# TubeAmp_driver.net
KiCad netlist of a schematic drawn in EAGLE
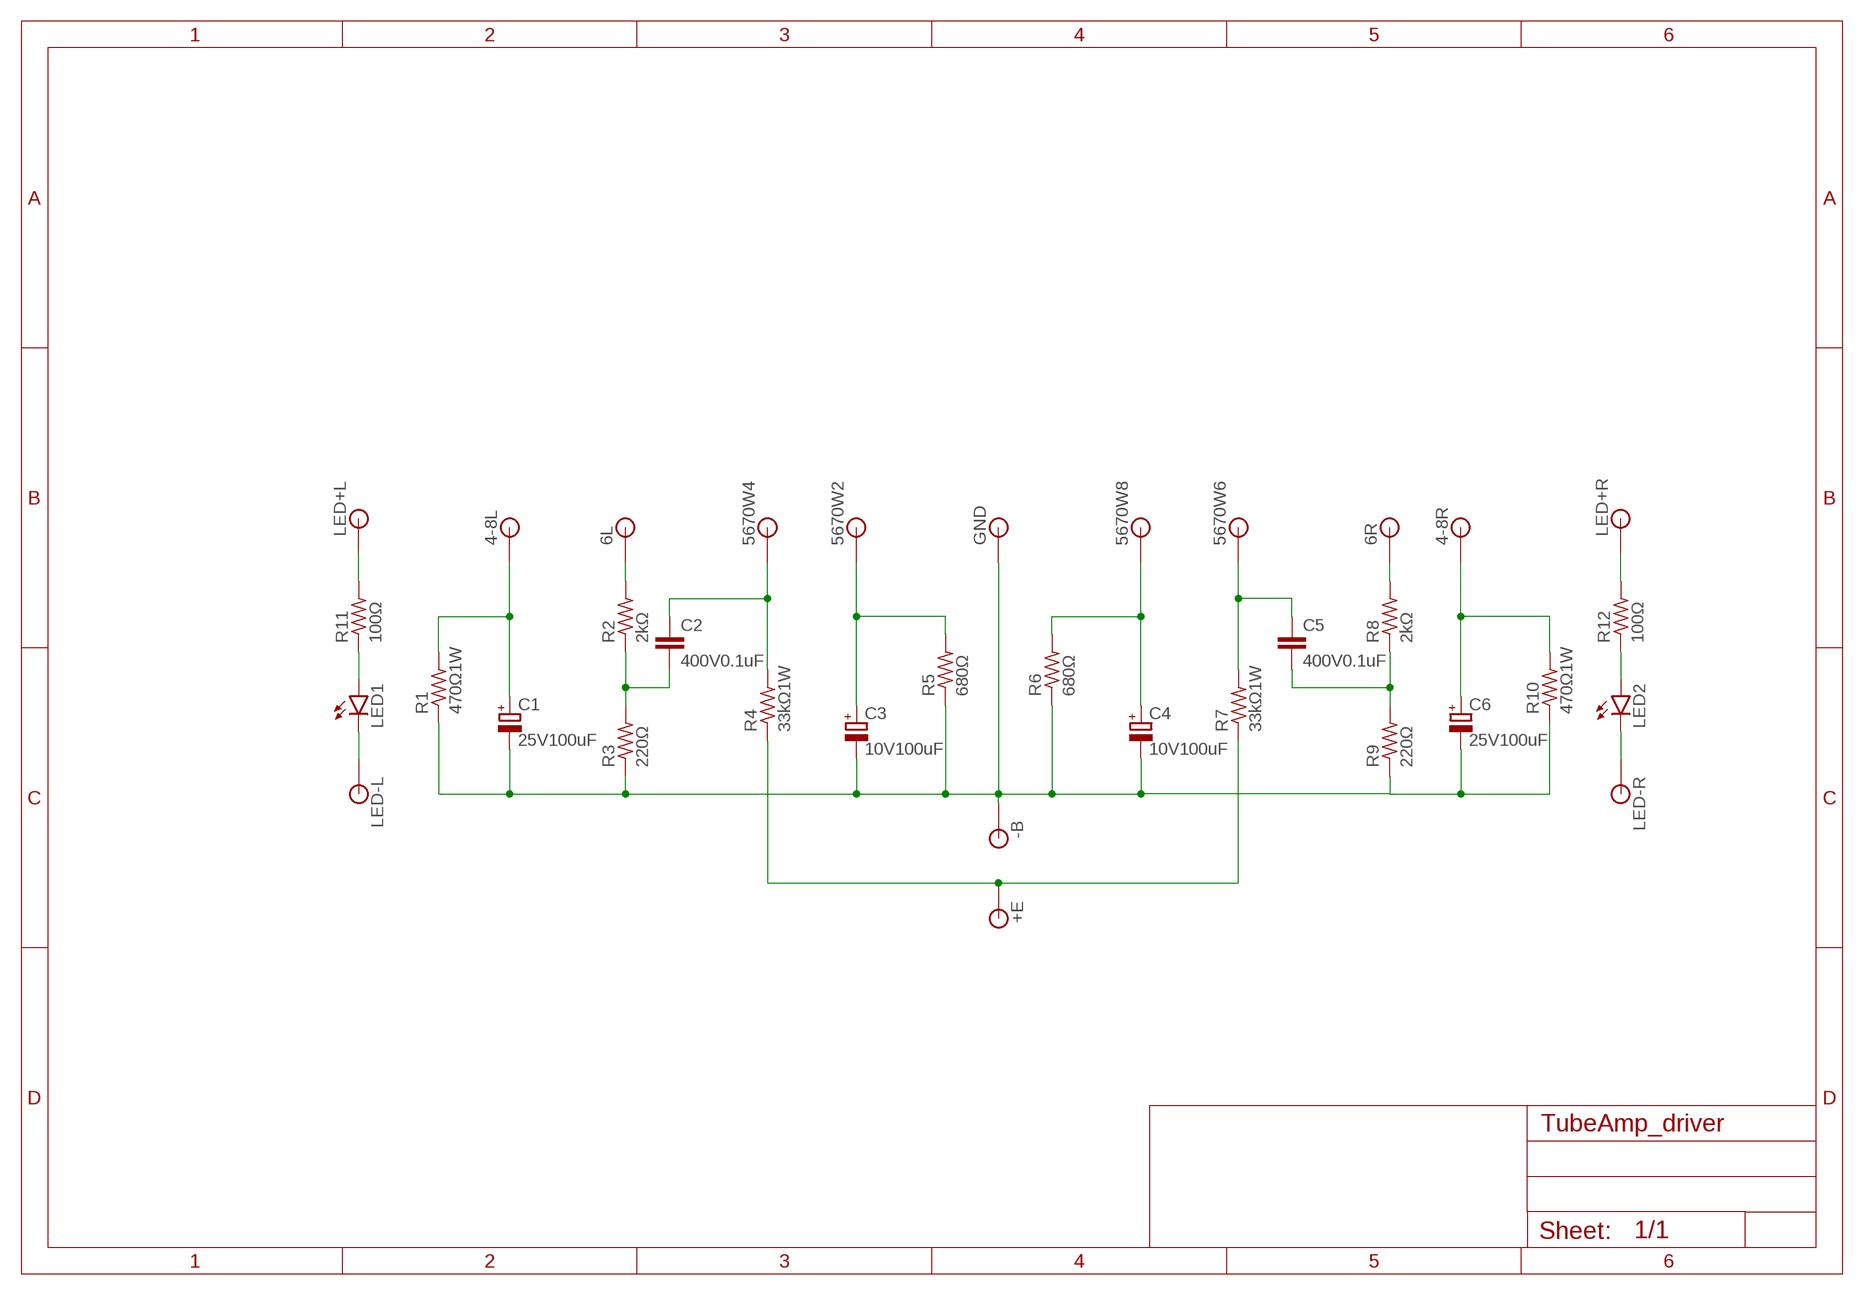
[diagram p0: schematic, sheet 1]

(export (version "E")
  (design (tool "Eeschema 10.0.6"))
  (components
    (comp (ref "+E")
      (value "PIN-1X11.2MM")
      (footprint "eagle-import:PIN-1X1_1.2MM")
      (libsource (lib "eagle-import") (part "PIN-1X11.2MM"))
    )
    (comp (ref "-B")
      (value "PIN-1X11.2MM")
      (footprint "eagle-import:PIN-1X1_1.2MM")
      (libsource (lib "eagle-import") (part "PIN-1X11.2MM"))
    )
    (comp (ref "4-8L")
      (value "PIN-1X11.2MM")
      (footprint "eagle-import:PIN-1X1_1.2MM")
      (libsource (lib "eagle-import") (part "PIN-1X11.2MM"))
    )
    (comp (ref "4-8R")
      (value "PIN-1X11.2MM")
      (footprint "eagle-import:PIN-1X1_1.2MM")
      (libsource (lib "eagle-import") (part "PIN-1X11.2MM"))
    )
    (comp (ref "6L")
      (value "PIN-1X11.2MM")
      (footprint "eagle-import:PIN-1X1_1.2MM")
      (libsource (lib "eagle-import") (part "PIN-1X11.2MM"))
    )
    (comp (ref "6R")
      (value "PIN-1X11.2MM")
      (footprint "eagle-import:PIN-1X1_1.2MM")
      (libsource (lib "eagle-import") (part "PIN-1X11.2MM"))
    )
    (comp (ref "5670W2")
      (value "PIN-1X11.2MM")
      (footprint "eagle-import:PIN-1X1_1.2MM")
      (libsource (lib "eagle-import") (part "PIN-1X11.2MM"))
    )
    (comp (ref "5670W4")
      (value "PIN-1X11.2MM")
      (footprint "eagle-import:PIN-1X1_1.2MM")
      (libsource (lib "eagle-import") (part "PIN-1X11.2MM"))
    )
    (comp (ref "5670W6")
      (value "PIN-1X11.2MM")
      (footprint "eagle-import:PIN-1X1_1.2MM")
      (libsource (lib "eagle-import") (part "PIN-1X11.2MM"))
    )
    (comp (ref "5670W8")
      (value "PIN-1X11.2MM")
      (footprint "eagle-import:PIN-1X1_1.2MM")
      (libsource (lib "eagle-import") (part "PIN-1X11.2MM"))
    )
    (comp (ref "C1")
      (value "25V100uF")
      (footprint "eagle-import:CPOL25_65")
      (libsource (lib "eagle-import") (part "CPOL25_65"))
    )
    (comp (ref "C2")
      (value "400V0.1uF")
      (footprint "eagle-import:C125_63X155")
      (libsource (lib "eagle-import") (part "C125_63X155"))
    )
    (comp (ref "C3")
      (value "10V100uF")
      (footprint "eagle-import:CPOL25_65")
      (libsource (lib "eagle-import") (part "CPOL25_65"))
    )
    (comp (ref "C4")
      (value "10V100uF")
      (footprint "eagle-import:CPOL25_65")
      (libsource (lib "eagle-import") (part "CPOL25_65"))
    )
    (comp (ref "C5")
      (value "400V0.1uF")
      (footprint "eagle-import:C125_63X155")
      (libsource (lib "eagle-import") (part "C125_63X155"))
    )
    (comp (ref "C6")
      (value "25V100uF")
      (footprint "eagle-import:CPOL25_65")
      (libsource (lib "eagle-import") (part "CPOL25_65"))
    )
    (comp (ref "GND")
      (value "PIN-1X11.2MM")
      (footprint "eagle-import:PIN-1X1_1.2MM")
      (libsource (lib "eagle-import") (part "PIN-1X11.2MM"))
    )
    (comp (ref "LED+L")
      (value "PIN-1X11.2MM")
      (footprint "eagle-import:PIN-1X1_1.2MM")
      (libsource (lib "eagle-import") (part "PIN-1X11.2MM"))
    )
    (comp (ref "LED+R")
      (value "PIN-1X11.2MM")
      (footprint "eagle-import:PIN-1X1_1.2MM")
      (libsource (lib "eagle-import") (part "PIN-1X11.2MM"))
    )
    (comp (ref "LED-L")
      (value "PIN-1X11.2MM")
      (footprint "eagle-import:PIN-1X1_1.2MM")
      (libsource (lib "eagle-import") (part "PIN-1X11.2MM"))
    )
    (comp (ref "LED-R")
      (value "PIN-1X11.2MM")
      (footprint "eagle-import:PIN-1X1_1.2MM")
      (libsource (lib "eagle-import") (part "PIN-1X11.2MM"))
    )
    (comp (ref "LED1")
      (value "LED-3MM")
      (footprint "eagle-import:LED-3MM")
      (libsource (lib "eagle-import") (part "LED-3MM"))
    )
    (comp (ref "LED2")
      (value "LED-3MM")
      (footprint "eagle-import:LED-3MM")
      (libsource (lib "eagle-import") (part "LED-3MM"))
    )
    (comp (ref "R1")
      (value "470Ω1W")
      (footprint "eagle-import:RESISTOR_1W")
      (libsource (lib "eagle-import") (part "RESISTOR1W"))
    )
    (comp (ref "R2")
      (value "2kΩ")
      (footprint "eagle-import:RESISTOR_1_4W")
      (libsource (lib "eagle-import") (part "RESISTOR1/4W"))
    )
    (comp (ref "R3")
      (value "220Ω")
      (footprint "eagle-import:RESISTOR_1_4W")
      (libsource (lib "eagle-import") (part "RESISTOR1/4W"))
    )
    (comp (ref "R4")
      (value "33kΩ1W")
      (footprint "eagle-import:RESISTOR_1W")
      (libsource (lib "eagle-import") (part "RESISTOR1W"))
    )
    (comp (ref "R5")
      (value "680Ω")
      (footprint "eagle-import:RESISTOR_1_4W")
      (libsource (lib "eagle-import") (part "RESISTOR1/4W"))
    )
    (comp (ref "R6")
      (value "680Ω")
      (footprint "eagle-import:RESISTOR_1_4W")
      (libsource (lib "eagle-import") (part "RESISTOR1/4W"))
    )
    (comp (ref "R7")
      (value "33kΩ1W")
      (footprint "eagle-import:RESISTOR_1W")
      (libsource (lib "eagle-import") (part "RESISTOR1W"))
    )
    (comp (ref "R8")
      (value "2kΩ")
      (footprint "eagle-import:RESISTOR_1_4W")
      (libsource (lib "eagle-import") (part "RESISTOR1/4W"))
    )
    (comp (ref "R9")
      (value "220Ω")
      (footprint "eagle-import:RESISTOR_1_4W")
      (libsource (lib "eagle-import") (part "RESISTOR1/4W"))
    )
    (comp (ref "R10")
      (value "470Ω1W")
      (footprint "eagle-import:RESISTOR_1W")
      (libsource (lib "eagle-import") (part "RESISTOR1W"))
    )
    (comp (ref "R11")
      (value "100Ω")
      (footprint "eagle-import:RESISTOR_1_4W")
      (libsource (lib "eagle-import") (part "RESISTOR1/4W"))
    )
    (comp (ref "R12")
      (value "100Ω")
      (footprint "eagle-import:RESISTOR_1_4W")
      (libsource (lib "eagle-import") (part "RESISTOR1/4W"))
    )
  )
  (nets
    (net (code "1") (name "Net-(+E-Pad1)") (class "Default")
      (node (ref "+E") (pin "1") (pinfunction "1_1") (pintype "bidirectional"))
      (node (ref "R4") (pin "1") (pinfunction "1_1") (pintype "passive"))
      (node (ref "R7") (pin "1") (pinfunction "1_1") (pintype "passive"))
    )
    (net (code "2") (name "Net-(-B-Pad1)") (class "Default")
      (node (ref "-B") (pin "1") (pinfunction "1_1") (pintype "bidirectional"))
      (node (ref "C1") (pin "-") (pinfunction "-_-") (pintype "passive"))
      (node (ref "C3") (pin "-") (pinfunction "-_-") (pintype "passive"))
      (node (ref "C4") (pin "-") (pinfunction "-_-") (pintype "passive"))
      (node (ref "C6") (pin "-") (pinfunction "-_-") (pintype "passive"))
      (node (ref "GND") (pin "1") (pinfunction "1_1") (pintype "bidirectional"))
      (node (ref "R1") (pin "1") (pinfunction "1_1") (pintype "passive"))
      (node (ref "R10") (pin "1") (pinfunction "1_1") (pintype "passive"))
      (node (ref "R3") (pin "1") (pinfunction "1_1") (pintype "passive"))
      (node (ref "R5") (pin "1") (pinfunction "1_1") (pintype "passive"))
      (node (ref "R6") (pin "1") (pinfunction "1_1") (pintype "passive"))
      (node (ref "R9") (pin "1") (pinfunction "1_1") (pintype "passive"))
    )
    (net (code "3") (name "Net-(4-8L-Pad1)") (class "Default")
      (node (ref "4-8L") (pin "1") (pinfunction "1_1") (pintype "bidirectional"))
      (node (ref "C1") (pin "+") (pinfunction "+_+") (pintype "passive"))
      (node (ref "R1") (pin "2") (pinfunction "2_2") (pintype "passive"))
    )
    (net (code "4") (name "Net-(4-8R-Pad1)") (class "Default")
      (node (ref "4-8R") (pin "1") (pinfunction "1_1") (pintype "bidirectional"))
      (node (ref "C6") (pin "+") (pinfunction "+_+") (pintype "passive"))
      (node (ref "R10") (pin "2") (pinfunction "2_2") (pintype "passive"))
    )
    (net (code "5") (name "Net-(6L-Pad1)") (class "Default")
      (node (ref "6L") (pin "1") (pinfunction "1_1") (pintype "bidirectional"))
      (node (ref "R2") (pin "2") (pinfunction "2_2") (pintype "passive"))
    )
    (net (code "6") (name "Net-(6R-Pad1)") (class "Default")
      (node (ref "6R") (pin "1") (pinfunction "1_1") (pintype "bidirectional"))
      (node (ref "R8") (pin "2") (pinfunction "2_2") (pintype "passive"))
    )
    (net (code "7") (name "Net-(5670W2-Pad1)") (class "Default")
      (node (ref "5670W2") (pin "1") (pinfunction "1_1") (pintype "bidirectional"))
      (node (ref "C3") (pin "+") (pinfunction "+_+") (pintype "passive"))
      (node (ref "R5") (pin "2") (pinfunction "2_2") (pintype "passive"))
    )
    (net (code "8") (name "Net-(5670W4-Pad1)") (class "Default")
      (node (ref "5670W4") (pin "1") (pinfunction "1_1") (pintype "bidirectional"))
      (node (ref "C2") (pin "1") (pinfunction "1_1") (pintype "passive"))
      (node (ref "R4") (pin "2") (pinfunction "2_2") (pintype "passive"))
    )
    (net (code "9") (name "Net-(5670W6-Pad1)") (class "Default")
      (node (ref "5670W6") (pin "1") (pinfunction "1_1") (pintype "bidirectional"))
      (node (ref "C5") (pin "1") (pinfunction "1_1") (pintype "passive"))
      (node (ref "R7") (pin "2") (pinfunction "2_2") (pintype "passive"))
    )
    (net (code "10") (name "Net-(5670W8-Pad1)") (class "Default")
      (node (ref "5670W8") (pin "1") (pinfunction "1_1") (pintype "bidirectional"))
      (node (ref "C4") (pin "+") (pinfunction "+_+") (pintype "passive"))
      (node (ref "R6") (pin "2") (pinfunction "2_2") (pintype "passive"))
    )
    (net (code "11") (name "Net-(C2-Pad2)") (class "Default")
      (node (ref "C2") (pin "2") (pinfunction "2_2") (pintype "passive"))
      (node (ref "R2") (pin "1") (pinfunction "1_1") (pintype "passive"))
      (node (ref "R3") (pin "2") (pinfunction "2_2") (pintype "passive"))
    )
    (net (code "12") (name "Net-(C5-Pad2)") (class "Default")
      (node (ref "C5") (pin "2") (pinfunction "2_2") (pintype "passive"))
      (node (ref "R8") (pin "1") (pinfunction "1_1") (pintype "passive"))
      (node (ref "R9") (pin "2") (pinfunction "2_2") (pintype "passive"))
    )
    (net (code "13") (name "Net-(LED+L-Pad1)") (class "Default")
      (node (ref "LED+L") (pin "1") (pinfunction "1_1") (pintype "bidirectional"))
      (node (ref "R11") (pin "2") (pinfunction "2_2") (pintype "passive"))
    )
    (net (code "14") (name "Net-(LED+R-Pad1)") (class "Default")
      (node (ref "LED+R") (pin "1") (pinfunction "1_1") (pintype "bidirectional"))
      (node (ref "R12") (pin "2") (pinfunction "2_2") (pintype "passive"))
    )
    (net (code "15") (name "Net-(LED1-C)") (class "Default")
      (node (ref "LED-L") (pin "1") (pinfunction "1_1") (pintype "bidirectional"))
      (node (ref "LED1") (pin "K") (pinfunction "C_K") (pintype "passive"))
    )
    (net (code "16") (name "Net-(LED1-PadA)") (class "Default")
      (node (ref "LED1") (pin "A") (pinfunction "A_A") (pintype "passive"))
      (node (ref "R11") (pin "1") (pinfunction "1_1") (pintype "passive"))
    )
    (net (code "17") (name "Net-(LED2-C)") (class "Default")
      (node (ref "LED-R") (pin "1") (pinfunction "1_1") (pintype "bidirectional"))
      (node (ref "LED2") (pin "K") (pinfunction "C_K") (pintype "passive"))
    )
    (net (code "18") (name "Net-(LED2-PadA)") (class "Default")
      (node (ref "LED2") (pin "A") (pinfunction "A_A") (pintype "passive"))
      (node (ref "R12") (pin "1") (pinfunction "1_1") (pintype "passive"))
    )
  )
)
